# ASR_USB.net
KiCad netlist of a schematic drawn in Altium Designer
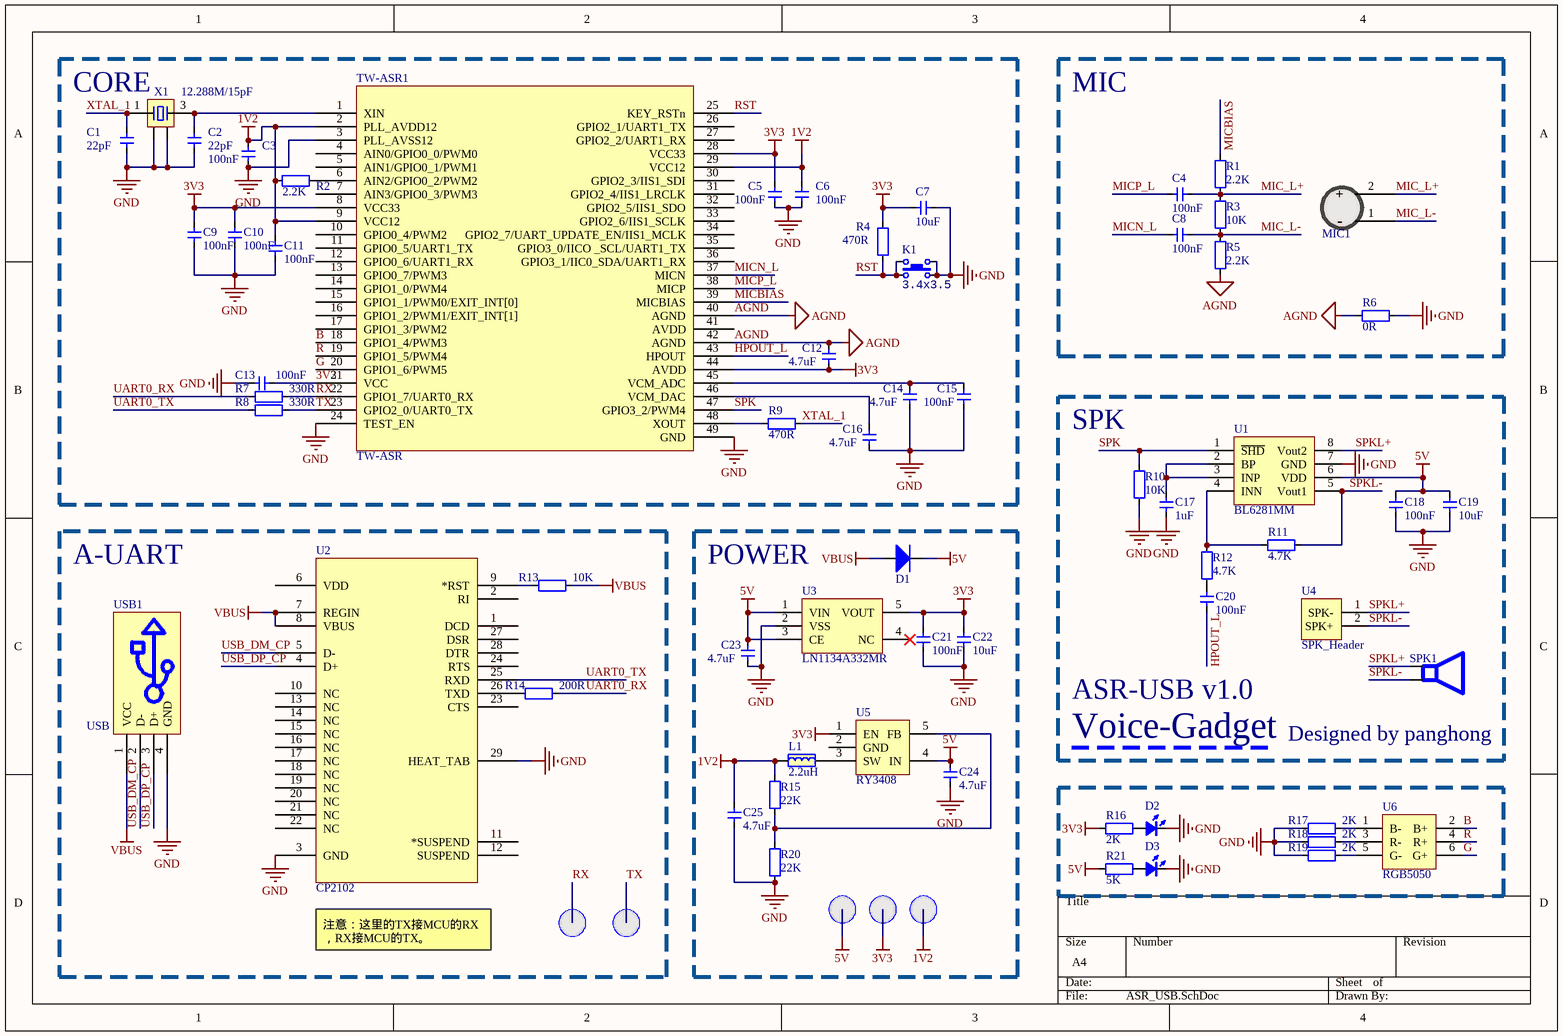
[diagram p0: ASR_USB.SchDoc]

(export (version "E")
  (design (tool "Eeschema 10.0.6"))
  (components
    (comp (ref "C1")
      (value "22pF")
      (footprint "CAP_0402")
      (description "Capacitor")
      (libsource (lib "Micius") (part "CAP-0402"))
    )
    (comp (ref "C2")
      (value "22pF")
      (footprint "CAP_0402")
      (description "Capacitor")
      (libsource (lib "Micius") (part "CAP-0402"))
    )
    (comp (ref "C3")
      (value "100nF")
      (footprint "CAP_0402")
      (description "Capacitor")
      (libsource (lib "Micius") (part "CAP-0402"))
    )
    (comp (ref "C4")
      (value "100nF")
      (footprint "CAP_0402")
      (description "Capacitor")
      (libsource (lib "Micius") (part "CAP-0402"))
    )
    (comp (ref "C5")
      (value "100nF")
      (footprint "CAP_0402")
      (description "Capacitor")
      (libsource (lib "Micius") (part "CAP-0402"))
    )
    (comp (ref "C6")
      (value "100nF")
      (footprint "CAP_0402")
      (description "Capacitor")
      (libsource (lib "Micius") (part "CAP-0402"))
    )
    (comp (ref "C7")
      (value "10uF")
      (footprint "CAP_0402")
      (description "Capacitor")
      (libsource (lib "Micius") (part "CAP-0402"))
    )
    (comp (ref "C8")
      (value "100nF")
      (footprint "CAP_0402")
      (description "Capacitor")
      (libsource (lib "Micius") (part "CAP-0402"))
    )
    (comp (ref "C9")
      (value "100nF")
      (footprint "CAP_0402")
      (description "Capacitor")
      (libsource (lib "Micius") (part "CAP-0402"))
    )
    (comp (ref "C10")
      (value "100nF")
      (footprint "CAP_0402")
      (description "Capacitor")
      (libsource (lib "Micius") (part "CAP-0402"))
    )
    (comp (ref "C11")
      (value "100nF")
      (footprint "CAP_0402")
      (description "Capacitor")
      (libsource (lib "Micius") (part "CAP-0402"))
    )
    (comp (ref "C12")
      (value "4.7uF")
      (footprint "CAP_0402")
      (description "Capacitor")
      (libsource (lib "Micius") (part "CAP-0402"))
    )
    (comp (ref "C13")
      (value "100nF")
      (footprint "CAP_0402")
      (description "Capacitor")
      (libsource (lib "Micius") (part "CAP-0402"))
    )
    (comp (ref "C14")
      (value "4.7uF")
      (footprint "CAP_0402")
      (description "Capacitor")
      (libsource (lib "Micius") (part "CAP-0402"))
    )
    (comp (ref "C15")
      (value "100nF")
      (footprint "CAP_0402")
      (description "Capacitor")
      (libsource (lib "Micius") (part "CAP-0402"))
    )
    (comp (ref "C16")
      (value "4.7uF")
      (footprint "CAP_0402")
      (description "Capacitor")
      (libsource (lib "Micius") (part "CAP-0402"))
    )
    (comp (ref "C17")
      (value "1uF")
      (footprint "CAP_0402")
      (description "Capacitor")
      (libsource (lib "Micius") (part "CAP-0402"))
    )
    (comp (ref "C18")
      (value "100nF")
      (footprint "CAP_0402")
      (description "Capacitor")
      (libsource (lib "Micius") (part "CAP-0402"))
    )
    (comp (ref "C19")
      (value "10uF")
      (footprint "CAP_0402")
      (description "Capacitor")
      (libsource (lib "Micius") (part "CAP-0402"))
    )
    (comp (ref "C20")
      (value "100nF")
      (footprint "CAP_0402")
      (description "Capacitor")
      (libsource (lib "Micius") (part "CAP-0402"))
    )
    (comp (ref "C21")
      (value "100nF")
      (footprint "CAP_0402")
      (description "Capacitor")
      (libsource (lib "Micius") (part "CAP-0402"))
    )
    (comp (ref "C22")
      (value "10uF")
      (footprint "CAP_0402")
      (description "Capacitor")
      (libsource (lib "Micius") (part "CAP-0402"))
    )
    (comp (ref "C23")
      (value "4.7uF")
      (footprint "CAP_0402")
      (description "Capacitor")
      (libsource (lib "Micius") (part "CAP-0402"))
    )
    (comp (ref "C24")
      (value "4.7uF")
      (footprint "CAP_0402")
      (description "Capacitor")
      (libsource (lib "Micius") (part "CAP-0402"))
    )
    (comp (ref "C25")
      (value "4.7uF")
      (footprint "CAP_0402")
      (description "Capacitor")
      (libsource (lib "Micius") (part "CAP-0402"))
    )
    (comp (ref "D1")
      (value "二极管-5819W")
      (footprint "SOD-323")
      (description "40V")
      (libsource (lib "Micius") (part "二极管-5819W"))
    )
    (comp (ref "D2")
      (value "color?")
      (footprint "LED_0402_RED")
      (description "LED")
      (libsource (lib "Micius") (part "LED_0402"))
    )
    (comp (ref "D3")
      (value "color?")
      (footprint "LED_0402_RED")
      (description "LED")
      (libsource (lib "Micius") (part "LED_0402"))
    )
    (comp (ref "K1")
      (value "3.4x3.5")
      (footprint "ButtonTACT_3.5*3.55_90")
      (description "Button")
      (fields (field (name "Comment") "TACT 4P"))
      (libsource (lib "Micius") (part "ButtonTACT"))
    )
    (comp (ref "L1")
      (value "2.2uH")
      (footprint "2520-L")
      (description "磁珠")
      (libsource (lib "Micius") (part "电感-2520"))
    )
    (comp (ref "MIC1") (value "MIC") (footprint "MIC-SMT") (libsource (lib "Micius") (part "MIC")))
    (comp (ref "R1")
      (value "2.2K")
      (footprint "RES_0402")
      (description "Resistor")
      (libsource (lib "") (part "RES-0402_1"))
    )
    (comp (ref "R2")
      (value "2.2K")
      (footprint "RES_0402")
      (description "Resistor")
      (libsource (lib "Micius") (part "RES-0402"))
    )
    (comp (ref "R3")
      (value "10K")
      (footprint "RES_0402")
      (description "Resistor")
      (libsource (lib "") (part "RES-0402_1"))
    )
    (comp (ref "R4")
      (value "470R")
      (footprint "RES_0402")
      (description "Resistor")
      (libsource (lib "") (part "RES-0402_1"))
    )
    (comp (ref "R5")
      (value "2.2K")
      (footprint "RES_0402")
      (description "Resistor")
      (libsource (lib "") (part "RES-0402_1"))
    )
    (comp (ref "R6")
      (value "0R")
      (footprint "RES_0402")
      (description "Resistor")
      (libsource (lib "") (part "RES-0402_2"))
    )
    (comp (ref "R7")
      (value "330R")
      (footprint "RES_0402")
      (description "Resistor")
      (libsource (lib "Micius") (part "RES-0402"))
    )
    (comp (ref "R8")
      (value "330R")
      (footprint "RES_0402")
      (description "Resistor")
      (libsource (lib "Micius") (part "RES-0402"))
    )
    (comp (ref "R9")
      (value "470R")
      (footprint "RES_0402")
      (description "Resistor")
      (libsource (lib "Micius") (part "RES-0402"))
    )
    (comp (ref "R10")
      (value "10K")
      (footprint "RES_0402")
      (description "Resistor")
      (libsource (lib "") (part "RES-0402_1"))
    )
    (comp (ref "R11")
      (value "4.7K")
      (footprint "RES_0402")
      (description "Resistor")
      (libsource (lib "") (part "RES-0402_2"))
    )
    (comp (ref "R12")
      (value "4.7K")
      (footprint "RES_0402")
      (description "Resistor")
      (libsource (lib "") (part "RES-0402_1"))
    )
    (comp (ref "R13")
      (value "10K")
      (footprint "RES_0402")
      (description "Resistor")
      (libsource (lib "Micius") (part "RES-0402"))
    )
    (comp (ref "R14")
      (value "200R")
      (footprint "RES_0402")
      (description "Resistor")
      (libsource (lib "Micius") (part "RES-0402"))
    )
    (comp (ref "R15")
      (value "22K")
      (footprint "RES_0402")
      (description "Resistor")
      (libsource (lib "") (part "RES-0402_1"))
    )
    (comp (ref "R16")
      (value "2K")
      (footprint "RES_0402")
      (description "Resistor")
      (libsource (lib "") (part "RES-0402_2"))
    )
    (comp (ref "R17")
      (value "2K")
      (footprint "RES_0402")
      (description "Resistor")
      (libsource (lib "") (part "RES-0402_2"))
    )
    (comp (ref "R18")
      (value "2K")
      (footprint "RES_0402")
      (description "Resistor")
      (libsource (lib "") (part "RES-0402_2"))
    )
    (comp (ref "R19")
      (value "2K")
      (footprint "RES_0402")
      (description "Resistor")
      (libsource (lib "") (part "RES-0402_2"))
    )
    (comp (ref "R20")
      (value "22K")
      (footprint "RES_0402")
      (description "Resistor")
      (libsource (lib "") (part "RES-0402_1"))
    )
    (comp (ref "R21")
      (value "5K")
      (footprint "RES_0402")
      (description "Resistor")
      (libsource (lib "") (part "RES-0402_2"))
    )
    (comp (ref "SPK1") (value "SPK") (footprint "SPK") (libsource (lib "Micius") (part "扬声器(喇叭)")))
    (comp (ref "T1") (value "测试点") (footprint "TEST_PT") (libsource (lib "Micius") (part "测试点")))
    (comp (ref "T2") (value "测试点") (footprint "TEST_PT") (libsource (lib "Micius") (part "测试点")))
    (comp (ref "T3") (value "测试点") (footprint "TEST_PT") (libsource (lib "Micius") (part "测试点")))
    (comp (ref "T4")
      (value "LinkPoint")
      (footprint "TEST_PT_Point")
      (libsource (lib "Micius") (part "LinkPoint"))
    )
    (comp (ref "T5")
      (value "LinkPoint")
      (footprint "TEST_PT_Point")
      (libsource (lib "Micius") (part "LinkPoint"))
    )
    (comp (ref "TW-ASR1")
      (value "TW-ASR")
      (footprint "QFN48 7X7_L")
      (libsource (lib "Micius") (part "TW-ASR"))
    )
    (comp (ref "U1") (value "BL6281MM") (footprint "MSOP8_M") (libsource (lib "Micius") (part "BL6281MM")))
    (comp (ref "U2")
      (value "CP2102")
      (footprint "QFN-28")
      (description "USB转TTL")
      (libsource (lib "Micius") (part "CP2102"))
    )
    (comp (ref "U3")
      (value "LN1134A332MR")
      (footprint "SOT23-5")
      (libsource (lib "Micius") (part "LN1134A332MR"))
    )
    (comp (ref "U4")
      (value "SPK_Header")
      (footprint "SPK_Header")
      (libsource (lib "Micius") (part "SPK_Header"))
    )
    (comp (ref "U5") (value "RY3408") (footprint "SOT23-5") (libsource (lib "Micius") (part "RY3408")))
    (comp (ref "U6") (value "RGB5050") (footprint "RGB5050") (libsource (lib "Micius") (part "RGB5050")))
    (comp (ref "USB1") (value "USB") (footprint "USB-plug1") (libsource (lib "Micius") (part "USB公头")))
    (comp (ref "X1")
      (value "12.288M/15pF")
      (footprint "OSC 3225-4P")
      (description "4脚无源晶振")
      (fields (field (name "版权归属") "封装库来自淘宝卖家 ID：黄晶宝石"))
      (libsource (lib "Micius") (part "XTAL-4P"))
    )
  )
  (nets
    (net (code "1") (name "/B") (class "Default")
      (node (ref "TW-ASR1") (pin "18") (pinfunction "GPIO1_4/PWM3_18") (pintype "passive"))
      (node (ref "U6") (pin "2") (pinfunction "B+_2") (pintype "passive"))
    )
    (net (code "2") (name "/G") (class "Default")
      (node (ref "TW-ASR1") (pin "20") (pinfunction "GPIO1_6/PWM5_20") (pintype "passive"))
      (node (ref "U6") (pin "6") (pinfunction "G+_6") (pintype "passive"))
    )
    (net (code "3") (name "/HPOUT_L") (class "Default")
      (node (ref "C20") (pin "2") (pinfunction "2_2") (pintype "passive"))
      (node (ref "TW-ASR1") (pin "43") (pinfunction "HPOUT_43") (pintype "passive"))
    )
    (net (code "4") (name "/MICBIAS") (class "Default")
      (node (ref "R1") (pin "2") (pinfunction "2_2") (pintype "passive"))
      (node (ref "TW-ASR1") (pin "39") (pinfunction "MICBIAS_39") (pintype "passive"))
    )
    (net (code "5") (name "/MICN_L") (class "Default")
      (node (ref "C8") (pin "2") (pinfunction "2_2") (pintype "passive"))
      (node (ref "TW-ASR1") (pin "37") (pinfunction "MICN_37") (pintype "passive"))
    )
    (net (code "6") (name "/MICP_L") (class "Default")
      (node (ref "C4") (pin "2") (pinfunction "2_2") (pintype "passive"))
      (node (ref "TW-ASR1") (pin "38") (pinfunction "MICP_38") (pintype "passive"))
    )
    (net (code "7") (name "/MIC_L+") (class "Default")
      (node (ref "C4") (pin "1") (pinfunction "1_1") (pintype "passive"))
      (node (ref "MIC1") (pin "2") (pinfunction "+_2") (pintype "passive"))
      (node (ref "R1") (pin "1") (pinfunction "1_1") (pintype "passive"))
      (node (ref "R3") (pin "2") (pinfunction "2_2") (pintype "passive"))
    )
    (net (code "8") (name "/MIC_L-") (class "Default")
      (node (ref "C8") (pin "1") (pinfunction "1_1") (pintype "passive"))
      (node (ref "MIC1") (pin "1") (pinfunction "-_1") (pintype "passive"))
      (node (ref "R3") (pin "1") (pinfunction "1_1") (pintype "passive"))
      (node (ref "R5") (pin "2") (pinfunction "2_2") (pintype "passive"))
    )
    (net (code "9") (name "/R") (class "Default")
      (node (ref "TW-ASR1") (pin "19") (pinfunction "GPIO1_5/PWM4_19") (pintype "passive"))
      (node (ref "U6") (pin "4") (pinfunction "R+_4") (pintype "passive"))
    )
    (net (code "10") (name "/RST") (class "Default")
      (node (ref "K1") (pin "1") (pinfunction "1_1") (pintype "passive"))
      (node (ref "K1") (pin "3") (pinfunction "3_3") (pintype "passive"))
      (node (ref "R4") (pin "1") (pinfunction "1_1") (pintype "passive"))
      (node (ref "TW-ASR1") (pin "25") (pinfunction "KEY_RSTn_25") (pintype "passive"))
    )
    (net (code "11") (name "/RX") (class "Default")
      (node (ref "R7") (pin "2") (pinfunction "2_2") (pintype "passive"))
      (node (ref "T4") (pin "0") (pinfunction "0_0") (pintype "passive"))
      (node (ref "TW-ASR1") (pin "22") (pinfunction "GPIO1_7/UART0_RX_22") (pintype "passive"))
    )
    (net (code "12") (name "/SPK") (class "Default")
      (node (ref "R10") (pin "2") (pinfunction "2_2") (pintype "passive"))
      (node (ref "TW-ASR1") (pin "47") (pinfunction "GPIO3_2/PWM4_47") (pintype "passive"))
      (node (ref "U1") (pin "1") (pinfunction "~{SHD}_1") (pintype "passive"))
    )
    (net (code "13") (name "/SPKL+") (class "Default")
      (node (ref "SPK1") (pin "1") (pinfunction "1_1") (pintype "passive"))
      (node (ref "U1") (pin "8") (pinfunction "Vout2_8") (pintype "passive"))
      (node (ref "U4") (pin "1") (pinfunction "SPK-_1") (pintype "passive"))
    )
    (net (code "14") (name "/SPKL-") (class "Default")
      (node (ref "R11") (pin "1") (pinfunction "1_1") (pintype "passive"))
      (node (ref "SPK1") (pin "2") (pinfunction "2_2") (pintype "passive"))
      (node (ref "U1") (pin "5") (pinfunction "Vout1_5") (pintype "passive"))
      (node (ref "U4") (pin "2") (pinfunction "SPK+_2") (pintype "passive"))
    )
    (net (code "15") (name "/TX") (class "Default")
      (node (ref "R8") (pin "2") (pinfunction "2_2") (pintype "passive"))
      (node (ref "T5") (pin "0") (pinfunction "0_0") (pintype "passive"))
      (node (ref "TW-ASR1") (pin "23") (pinfunction "GPIO2_0/UART0_TX_23") (pintype "passive"))
    )
    (net (code "16") (name "/UART0_RX") (class "Default")
      (node (ref "R14") (pin "2") (pinfunction "2_2") (pintype "passive"))
      (node (ref "R7") (pin "1") (pinfunction "1_1") (pintype "passive"))
    )
    (net (code "17") (name "/UART0_TX") (class "Default")
      (node (ref "R8") (pin "1") (pinfunction "1_1") (pintype "passive"))
      (node (ref "U2") (pin "25") (pinfunction "RXD_25") (pintype "passive"))
    )
    (net (code "18") (name "/USB_DM_CP") (class "Default")
      (node (ref "U2") (pin "5") (pinfunction "D-_5") (pintype "passive"))
      (node (ref "USB1") (pin "2") (pinfunction "D-_2") (pintype "passive"))
    )
    (net (code "19") (name "/USB_DP_CP") (class "Default")
      (node (ref "U2") (pin "4") (pinfunction "D+_4") (pintype "passive"))
      (node (ref "USB1") (pin "3") (pinfunction "D+_3") (pintype "passive"))
    )
    (net (code "20") (name "/XTAL_1") (class "Default")
      (node (ref "C1") (pin "2") (pinfunction "2_2") (pintype "passive"))
      (node (ref "R9") (pin "2") (pinfunction "2_2") (pintype "passive"))
      (node (ref "X1") (pin "1") (pinfunction "1_1") (pintype "passive"))
    )
    (net (code "21") (name "1V2") (class "Default")
      (node (ref "C11") (pin "1") (pinfunction "1_1") (pintype "passive"))
      (node (ref "C25") (pin "1") (pinfunction "1_1") (pintype "passive"))
      (node (ref "C3") (pin "2") (pinfunction "2_2") (pintype "passive"))
      (node (ref "C6") (pin "2") (pinfunction "2_2") (pintype "passive"))
      (node (ref "L1") (pin "1") (pintype "passive"))
      (node (ref "R15") (pin "2") (pinfunction "2_2") (pintype "passive"))
      (node (ref "R2") (pin "1") (pinfunction "1_1") (pintype "passive"))
      (node (ref "T3") (pin "0") (pinfunction "0_0") (pintype "passive"))
      (node (ref "TW-ASR1") (pin "2") (pinfunction "PLL_AVDD12_2") (pintype "passive"))
      (node (ref "TW-ASR1") (pin "29") (pinfunction "VCC12_29") (pintype "passive"))
      (node (ref "TW-ASR1") (pin "9") (pinfunction "VCC12_9") (pintype "passive"))
    )
    (net (code "22") (name "3V3") (class "Default")
      (node (ref "C10") (pin "1") (pinfunction "1_1") (pintype "passive"))
      (node (ref "C12") (pin "1") (pinfunction "1_1") (pintype "passive"))
      (node (ref "C13") (pin "1") (pinfunction "1_1") (pintype "passive"))
      (node (ref "C21") (pin "1") (pinfunction "1_1") (pintype "passive"))
      (node (ref "C22") (pin "1") (pinfunction "1_1") (pintype "passive"))
      (node (ref "C5") (pin "2") (pinfunction "2_2") (pintype "passive"))
      (node (ref "C7") (pin "2") (pinfunction "2_2") (pintype "passive"))
      (node (ref "C9") (pin "1") (pinfunction "1_1") (pintype "passive"))
      (node (ref "R16") (pin "2") (pinfunction "2_2") (pintype "passive"))
      (node (ref "R4") (pin "2") (pinfunction "2_2") (pintype "passive"))
      (node (ref "T2") (pin "0") (pinfunction "0_0") (pintype "passive"))
      (node (ref "TW-ASR1") (pin "21") (pinfunction "VCC_21") (pintype "passive"))
      (node (ref "TW-ASR1") (pin "28") (pinfunction "VCC33_28") (pintype "passive"))
      (node (ref "TW-ASR1") (pin "44") (pinfunction "AVDD_44") (pintype "passive"))
      (node (ref "TW-ASR1") (pin "8") (pinfunction "VCC33_8") (pintype "passive"))
      (node (ref "U3") (pin "5") (pinfunction "VOUT_5") (pintype "passive"))
      (node (ref "U5") (pin "1") (pinfunction "EN_1") (pintype "passive"))
    )
    (net (code "23") (name "5V") (class "Default")
      (node (ref "C18") (pin "1") (pinfunction "1_1") (pintype "passive"))
      (node (ref "C19") (pin "1") (pinfunction "1_1") (pintype "passive"))
      (node (ref "C23") (pin "2") (pinfunction "2_2") (pintype "passive"))
      (node (ref "C24") (pin "1") (pinfunction "1_1") (pintype "passive"))
      (node (ref "D1") (pin "2") (pinfunction "K_2") (pintype "passive"))
      (node (ref "R21") (pin "2") (pinfunction "2_2") (pintype "passive"))
      (node (ref "T1") (pin "0") (pinfunction "0_0") (pintype "passive"))
      (node (ref "U1") (pin "6") (pinfunction "VDD_6") (pintype "passive"))
      (node (ref "U3") (pin "1") (pinfunction "VIN_1") (pintype "passive"))
      (node (ref "U3") (pin "3") (pinfunction "CE_3") (pintype "passive"))
      (node (ref "U5") (pin "4") (pinfunction "IN_4") (pintype "passive"))
    )
    (net (code "24") (name "AGND") (class "Default")
      (node (ref "C12") (pin "2") (pinfunction "2_2") (pintype "passive"))
      (node (ref "R5") (pin "1") (pinfunction "1_1") (pintype "passive"))
      (node (ref "R6") (pin "2") (pinfunction "2_2") (pintype "passive"))
      (node (ref "TW-ASR1") (pin "40") (pinfunction "AGND_40") (pintype "passive"))
      (node (ref "TW-ASR1") (pin "42") (pinfunction "AGND_42") (pintype "passive"))
    )
    (net (code "25") (name "GND") (class "Default")
      (node (ref "C1") (pin "1") (pinfunction "1_1") (pintype "passive"))
      (node (ref "C10") (pin "2") (pinfunction "2_2") (pintype "passive"))
      (node (ref "C11") (pin "2") (pinfunction "2_2") (pintype "passive"))
      (node (ref "C13") (pin "2") (pinfunction "2_2") (pintype "passive"))
      (node (ref "C14") (pin "1") (pinfunction "1_1") (pintype "passive"))
      (node (ref "C15") (pin "1") (pinfunction "1_1") (pintype "passive"))
      (node (ref "C16") (pin "1") (pinfunction "1_1") (pintype "passive"))
      (node (ref "C17") (pin "2") (pinfunction "2_2") (pintype "passive"))
      (node (ref "C18") (pin "2") (pinfunction "2_2") (pintype "passive"))
      (node (ref "C19") (pin "2") (pinfunction "2_2") (pintype "passive"))
      (node (ref "C2") (pin "1") (pinfunction "1_1") (pintype "passive"))
      (node (ref "C21") (pin "2") (pinfunction "2_2") (pintype "passive"))
      (node (ref "C22") (pin "2") (pinfunction "2_2") (pintype "passive"))
      (node (ref "C23") (pin "1") (pinfunction "1_1") (pintype "passive"))
      (node (ref "C24") (pin "2") (pinfunction "2_2") (pintype "passive"))
      (node (ref "C25") (pin "2") (pinfunction "2_2") (pintype "passive"))
      (node (ref "C3") (pin "1") (pinfunction "1_1") (pintype "passive"))
      (node (ref "C5") (pin "1") (pinfunction "1_1") (pintype "passive"))
      (node (ref "C6") (pin "1") (pinfunction "1_1") (pintype "passive"))
      (node (ref "C7") (pin "1") (pinfunction "1_1") (pintype "passive"))
      (node (ref "C9") (pin "2") (pinfunction "2_2") (pintype "passive"))
      (node (ref "D2") (pin "2") (pinfunction "K_2") (pintype "passive"))
      (node (ref "D3") (pin "2") (pinfunction "K_2") (pintype "passive"))
      (node (ref "K1") (pin "2") (pinfunction "2_2") (pintype "passive"))
      (node (ref "K1") (pin "4") (pinfunction "4_4") (pintype "passive"))
      (node (ref "R10") (pin "1") (pinfunction "1_1") (pintype "passive"))
      (node (ref "R17") (pin "2") (pinfunction "2_2") (pintype "passive"))
      (node (ref "R18") (pin "2") (pinfunction "2_2") (pintype "passive"))
      (node (ref "R19") (pin "2") (pinfunction "2_2") (pintype "passive"))
      (node (ref "R20") (pin "1") (pinfunction "1_1") (pintype "passive"))
      (node (ref "R6") (pin "1") (pinfunction "1_1") (pintype "passive"))
      (node (ref "TW-ASR1") (pin "24") (pinfunction "TEST_EN_24") (pintype "passive"))
      (node (ref "TW-ASR1") (pin "3") (pinfunction "PLL_AVSS12_3") (pintype "passive"))
      (node (ref "TW-ASR1") (pin "49") (pinfunction "GND_49") (pintype "passive"))
      (node (ref "U1") (pin "7") (pinfunction "GND_7") (pintype "passive"))
      (node (ref "U2") (pin "29") (pinfunction "HEAT_TAB_29") (pintype "passive"))
      (node (ref "U2") (pin "3") (pinfunction "GND_3") (pintype "passive"))
      (node (ref "U3") (pin "2") (pinfunction "VSS_2") (pintype "passive"))
      (node (ref "USB1") (pin "4") (pinfunction "GND_4") (pintype "passive"))
      (node (ref "X1") (pin "2") (pinfunction "2_2") (pintype "passive"))
      (node (ref "X1") (pin "4") (pinfunction "4_4") (pintype "passive"))
    )
    (net (code "26") (name "Net-(C20-Pad1)") (class "Default")
      (node (ref "C20") (pin "1") (pinfunction "1_1") (pintype "passive"))
      (node (ref "R12") (pin "1") (pinfunction "1_1") (pintype "passive"))
    )
    (net (code "27") (name "Net-(D2-A)") (class "Default")
      (node (ref "D2") (pin "1") (pinfunction "A_1") (pintype "passive"))
      (node (ref "R16") (pin "1") (pinfunction "1_1") (pintype "passive"))
    )
    (net (code "28") (name "Net-(D3-A)") (class "Default")
      (node (ref "D3") (pin "1") (pinfunction "A_1") (pintype "passive"))
      (node (ref "R21") (pin "1") (pinfunction "1_1") (pintype "passive"))
    )
    (net (code "29") (name "Net-(TW-ASR1-AIN2{slash}GPIO0_2{slash}PWM2)") (class "Default")
      (node (ref "R2") (pin "2") (pinfunction "2_2") (pintype "passive"))
      (node (ref "TW-ASR1") (pin "6") (pinfunction "AIN2/GPIO0_2/PWM2_6") (pintype "passive"))
    )
    (net (code "30") (name "Net-(TW-ASR1-VCM_ADC)") (class "Default")
      (node (ref "C14") (pin "2") (pinfunction "2_2") (pintype "passive"))
      (node (ref "C15") (pin "2") (pinfunction "2_2") (pintype "passive"))
      (node (ref "TW-ASR1") (pin "45") (pinfunction "VCM_ADC_45") (pintype "passive"))
    )
    (net (code "31") (name "Net-(TW-ASR1-VCM_DAC)") (class "Default")
      (node (ref "C16") (pin "2") (pinfunction "2_2") (pintype "passive"))
      (node (ref "TW-ASR1") (pin "46") (pinfunction "VCM_DAC_46") (pintype "passive"))
    )
    (net (code "32") (name "Net-(TW-ASR1-XIN)") (class "Default")
      (node (ref "C2") (pin "2") (pinfunction "2_2") (pintype "passive"))
      (node (ref "TW-ASR1") (pin "1") (pinfunction "XIN_1") (pintype "passive"))
      (node (ref "X1") (pin "3") (pinfunction "3_3") (pintype "passive"))
    )
    (net (code "33") (name "Net-(TW-ASR1-XOUT)") (class "Default")
      (node (ref "R9") (pin "1") (pinfunction "1_1") (pintype "passive"))
      (node (ref "TW-ASR1") (pin "48") (pinfunction "XOUT_48") (pintype "passive"))
    )
    (net (code "34") (name "Net-(U1-BP)") (class "Default")
      (node (ref "C17") (pin "1") (pinfunction "1_1") (pintype "passive"))
      (node (ref "U1") (pin "2") (pinfunction "BP_2") (pintype "passive"))
      (node (ref "U1") (pin "3") (pinfunction "INP_3") (pintype "passive"))
    )
    (net (code "35") (name "Net-(U1-INN)") (class "Default")
      (node (ref "R11") (pin "2") (pinfunction "2_2") (pintype "passive"))
      (node (ref "R12") (pin "2") (pinfunction "2_2") (pintype "passive"))
      (node (ref "U1") (pin "4") (pinfunction "INN_4") (pintype "passive"))
    )
    (net (code "36") (name "Net-(U2-*RST)") (class "Default")
      (node (ref "R13") (pin "1") (pinfunction "1_1") (pintype "passive"))
      (node (ref "U2") (pin "9") (pinfunction "*RST_9") (pintype "passive"))
    )
    (net (code "37") (name "Net-(U2-TXD)") (class "Default")
      (node (ref "R14") (pin "1") (pinfunction "1_1") (pintype "passive"))
      (node (ref "U2") (pin "26") (pinfunction "TXD_26") (pintype "passive"))
    )
    (net (code "38") (name "Net-(U5-FB)") (class "Default")
      (node (ref "R15") (pin "1") (pinfunction "1_1") (pintype "passive"))
      (node (ref "R20") (pin "2") (pinfunction "2_2") (pintype "passive"))
      (node (ref "U5") (pin "5") (pinfunction "FB_5") (pintype "passive"))
    )
    (net (code "39") (name "Net-(U5-SW)") (class "Default")
      (node (ref "L1") (pin "2") (pinfunction "2_2") (pintype "passive"))
      (node (ref "U5") (pin "3") (pinfunction "SW_3") (pintype "passive"))
    )
    (net (code "40") (name "Net-(U6-B-)") (class "Default")
      (node (ref "R17") (pin "1") (pinfunction "1_1") (pintype "passive"))
      (node (ref "U6") (pin "1") (pinfunction "B-_1") (pintype "passive"))
    )
    (net (code "41") (name "Net-(U6-G-)") (class "Default")
      (node (ref "R19") (pin "1") (pinfunction "1_1") (pintype "passive"))
      (node (ref "U6") (pin "5") (pinfunction "G-_5") (pintype "passive"))
    )
    (net (code "42") (name "Net-(U6-R-)") (class "Default")
      (node (ref "R18") (pin "1") (pinfunction "1_1") (pintype "passive"))
      (node (ref "U6") (pin "3") (pinfunction "R-_3") (pintype "passive"))
    )
    (net (code "43") (name "VBUS") (class "Default")
      (node (ref "D1") (pin "1") (pinfunction "A_1") (pintype "passive"))
      (node (ref "R13") (pin "2") (pinfunction "2_2") (pintype "passive"))
      (node (ref "U2") (pin "7") (pinfunction "REGIN_7") (pintype "passive"))
      (node (ref "U2") (pin "8") (pinfunction "VBUS_8") (pintype "passive"))
      (node (ref "USB1") (pin "1") (pinfunction "VCC_1") (pintype "passive"))
    )
    (net (code "44") (name "unconnected-(TW-ASR1-AIN0{slash}GPIO0_0{slash}PWM0-Pad4)") (class "Default")
      (node (ref "TW-ASR1") (pin "4") (pinfunction "AIN0/GPIO0_0/PWM0_4") (pintype "passive"))
    )
    (net (code "45") (name "unconnected-(TW-ASR1-AIN1{slash}GPIO0_1{slash}PWM1-Pad5)") (class "Default")
      (node (ref "TW-ASR1") (pin "5") (pinfunction "AIN1/GPIO0_1/PWM1_5") (pintype "passive"))
    )
    (net (code "46") (name "unconnected-(TW-ASR1-AIN3{slash}GPIO0_3{slash}PWM3-Pad7)") (class "Default")
      (node (ref "TW-ASR1") (pin "7") (pinfunction "AIN3/GPIO0_3/PWM3_7") (pintype "passive"))
    )
    (net (code "47") (name "unconnected-(TW-ASR1-AVDD-Pad41)") (class "Default")
      (node (ref "TW-ASR1") (pin "41") (pinfunction "AVDD_41") (pintype "passive"))
    )
    (net (code "48") (name "unconnected-(TW-ASR1-GPIO0_4{slash}PWM2-Pad10)") (class "Default")
      (node (ref "TW-ASR1") (pin "10") (pinfunction "GPIO0_4/PWM2_10") (pintype "passive"))
    )
    (net (code "49") (name "unconnected-(TW-ASR1-GPIO0_5{slash}UART1_TX-Pad11)") (class "Default")
      (node (ref "TW-ASR1") (pin "11") (pinfunction "GPIO0_5/UART1_TX_11") (pintype "passive"))
    )
    (net (code "50") (name "unconnected-(TW-ASR1-GPIO0_6{slash}UART1_RX-Pad12)") (class "Default")
      (node (ref "TW-ASR1") (pin "12") (pinfunction "GPIO0_6/UART1_RX_12") (pintype "passive"))
    )
    (net (code "51") (name "unconnected-(TW-ASR1-GPIO0_7{slash}PWM3-Pad13)") (class "Default")
      (node (ref "TW-ASR1") (pin "13") (pinfunction "GPIO0_7/PWM3_13") (pintype "passive"))
    )
    (net (code "52") (name "unconnected-(TW-ASR1-GPIO1_0{slash}PWM4-Pad14)") (class "Default")
      (node (ref "TW-ASR1") (pin "14") (pinfunction "GPIO1_0/PWM4_14") (pintype "passive"))
    )
    (net (code "53") (name "unconnected-(TW-ASR1-GPIO1_1{slash}PWM0{slash}EXIT_INT[0]-Pad15)") (class "Default")
      (node (ref "TW-ASR1") (pin "15") (pinfunction "GPIO1_1/PWM0/EXIT_INT[0]_15") (pintype "passive"))
    )
    (net (code "54") (name "unconnected-(TW-ASR1-GPIO1_2{slash}PWM1{slash}EXIT_INT[1]-Pad16)") (class "Default")
      (node (ref "TW-ASR1") (pin "16") (pinfunction "GPIO1_2/PWM1/EXIT_INT[1]_16") (pintype "passive"))
    )
    (net (code "55") (name "unconnected-(TW-ASR1-GPIO1_3{slash}PWM2-Pad17)") (class "Default")
      (node (ref "TW-ASR1") (pin "17") (pinfunction "GPIO1_3/PWM2_17") (pintype "passive"))
    )
    (net (code "56") (name "unconnected-(TW-ASR1-GPIO2_1{slash}UART1_TX-Pad26)") (class "Default")
      (node (ref "TW-ASR1") (pin "26") (pinfunction "GPIO2_1/UART1_TX_26") (pintype "passive"))
    )
    (net (code "57") (name "unconnected-(TW-ASR1-GPIO2_2{slash}UART1_RX-Pad27)") (class "Default")
      (node (ref "TW-ASR1") (pin "27") (pinfunction "GPIO2_2/UART1_RX_27") (pintype "passive"))
    )
    (net (code "58") (name "unconnected-(TW-ASR1-GPIO2_3{slash}IIS1_SDI-Pad30)") (class "Default")
      (node (ref "TW-ASR1") (pin "30") (pinfunction "GPIO2_3/IIS1_SDI_30") (pintype "passive"))
    )
    (net (code "59") (name "unconnected-(TW-ASR1-GPIO2_4{slash}IIS1_LRCLK-Pad31)") (class "Default")
      (node (ref "TW-ASR1") (pin "31") (pinfunction "GPIO2_4/IIS1_LRCLK_31") (pintype "passive"))
    )
    (net (code "60") (name "unconnected-(TW-ASR1-GPIO2_5{slash}IIS1_SDO-Pad32)") (class "Default")
      (node (ref "TW-ASR1") (pin "32") (pinfunction "GPIO2_5/IIS1_SDO_32") (pintype "passive"))
    )
    (net (code "61") (name "unconnected-(TW-ASR1-GPIO2_6{slash}IIS1_SCLK-Pad33)") (class "Default")
      (node (ref "TW-ASR1") (pin "33") (pinfunction "GPIO2_6/IIS1_SCLK_33") (pintype "passive"))
    )
    (net (code "62") (name "unconnected-(TW-ASR1-GPIO2_7{slash}UART_UPDATE_EN{slash}IIS1_MCLK-Pad34)") (class "Default")
      (node (ref "TW-ASR1") (pin "34") (pinfunction "GPIO2_7/UART_UPDATE_EN/IIS1_MCLK_34") (pintype "passive"))
    )
    (net (code "63") (name "unconnected-(TW-ASR1-GPIO3_0{slash}IICO__SCL{slash}UART1_TX-Pad35)") (class "Default")
      (node (ref "TW-ASR1") (pin "35") (pinfunction "GPIO3_0/IICO__SCL/UART1_TX_35") (pintype "passive"))
    )
    (net (code "64") (name "unconnected-(TW-ASR1-GPIO3_1{slash}IIC0_SDA{slash}UART1_RX-Pad36)") (class "Default")
      (node (ref "TW-ASR1") (pin "36") (pinfunction "GPIO3_1/IIC0_SDA/UART1_RX_36") (pintype "passive"))
    )
    (net (code "65") (name "unconnected-(U2-*SUSPEND-Pad11)") (class "Default")
      (node (ref "U2") (pin "11") (pinfunction "*SUSPEND_11") (pintype "passive"))
    )
    (net (code "66") (name "unconnected-(U2-CTS-Pad23)") (class "Default")
      (node (ref "U2") (pin "23") (pinfunction "CTS_23") (pintype "passive"))
    )
    (net (code "67") (name "unconnected-(U2-DCD-Pad1)") (class "Default")
      (node (ref "U2") (pin "1") (pinfunction "DCD_1") (pintype "passive"))
    )
    (net (code "68") (name "unconnected-(U2-DSR-Pad27)") (class "Default")
      (node (ref "U2") (pin "27") (pinfunction "DSR_27") (pintype "passive"))
    )
    (net (code "69") (name "unconnected-(U2-DTR-Pad28)") (class "Default")
      (node (ref "U2") (pin "28") (pinfunction "DTR_28") (pintype "passive"))
    )
    (net (code "70") (name "unconnected-(U2-NC-Pad10)") (class "Default")
      (node (ref "U2") (pin "10") (pinfunction "NC_10") (pintype "passive"))
    )
    (net (code "71") (name "unconnected-(U2-NC-Pad13)") (class "Default")
      (node (ref "U2") (pin "13") (pinfunction "NC_13") (pintype "passive"))
    )
    (net (code "72") (name "unconnected-(U2-NC-Pad14)") (class "Default")
      (node (ref "U2") (pin "14") (pinfunction "NC_14") (pintype "passive"))
    )
    (net (code "73") (name "unconnected-(U2-NC-Pad15)") (class "Default")
      (node (ref "U2") (pin "15") (pinfunction "NC_15") (pintype "passive"))
    )
    (net (code "74") (name "unconnected-(U2-NC-Pad16)") (class "Default")
      (node (ref "U2") (pin "16") (pinfunction "NC_16") (pintype "passive"))
    )
    (net (code "75") (name "unconnected-(U2-NC-Pad17)") (class "Default")
      (node (ref "U2") (pin "17") (pinfunction "NC_17") (pintype "passive"))
    )
    (net (code "76") (name "unconnected-(U2-NC-Pad18)") (class "Default")
      (node (ref "U2") (pin "18") (pinfunction "NC_18") (pintype "passive"))
    )
    (net (code "77") (name "unconnected-(U2-NC-Pad19)") (class "Default")
      (node (ref "U2") (pin "19") (pinfunction "NC_19") (pintype "passive"))
    )
    (net (code "78") (name "unconnected-(U2-NC-Pad20)") (class "Default")
      (node (ref "U2") (pin "20") (pinfunction "NC_20") (pintype "passive"))
    )
    (net (code "79") (name "unconnected-(U2-NC-Pad21)") (class "Default")
      (node (ref "U2") (pin "21") (pinfunction "NC_21") (pintype "passive"))
    )
    (net (code "80") (name "unconnected-(U2-NC-Pad22)") (class "Default")
      (node (ref "U2") (pin "22") (pinfunction "NC_22") (pintype "passive"))
    )
    (net (code "81") (name "unconnected-(U2-RI-Pad2)") (class "Default")
      (node (ref "U2") (pin "2") (pinfunction "RI_2") (pintype "passive"))
    )
    (net (code "82") (name "unconnected-(U2-RTS-Pad24)") (class "Default")
      (node (ref "U2") (pin "24") (pinfunction "RTS_24") (pintype "passive"))
    )
    (net (code "83") (name "unconnected-(U2-SUSPEND-Pad12)") (class "Default")
      (node (ref "U2") (pin "12") (pinfunction "SUSPEND_12") (pintype "passive"))
    )
    (net (code "84") (name "unconnected-(U2-VDD-Pad6)") (class "Default")
      (node (ref "U2") (pin "6") (pinfunction "VDD_6") (pintype "passive"))
    )
    (net (code "85") (name "unconnected-(U3-NC-Pad4)") (class "Default")
      (node (ref "U3") (pin "4") (pinfunction "NC_4") (pintype "passive+no_connect"))
    )
    (net (code "86") (name "unconnected-(U5-GND-Pad2)") (class "Default")
      (node (ref "U5") (pin "2") (pinfunction "GND_2") (pintype "passive"))
    )
  )
)
